# Lab1_Schematics.net
KiCad netlist of a schematic drawn in EAGLE
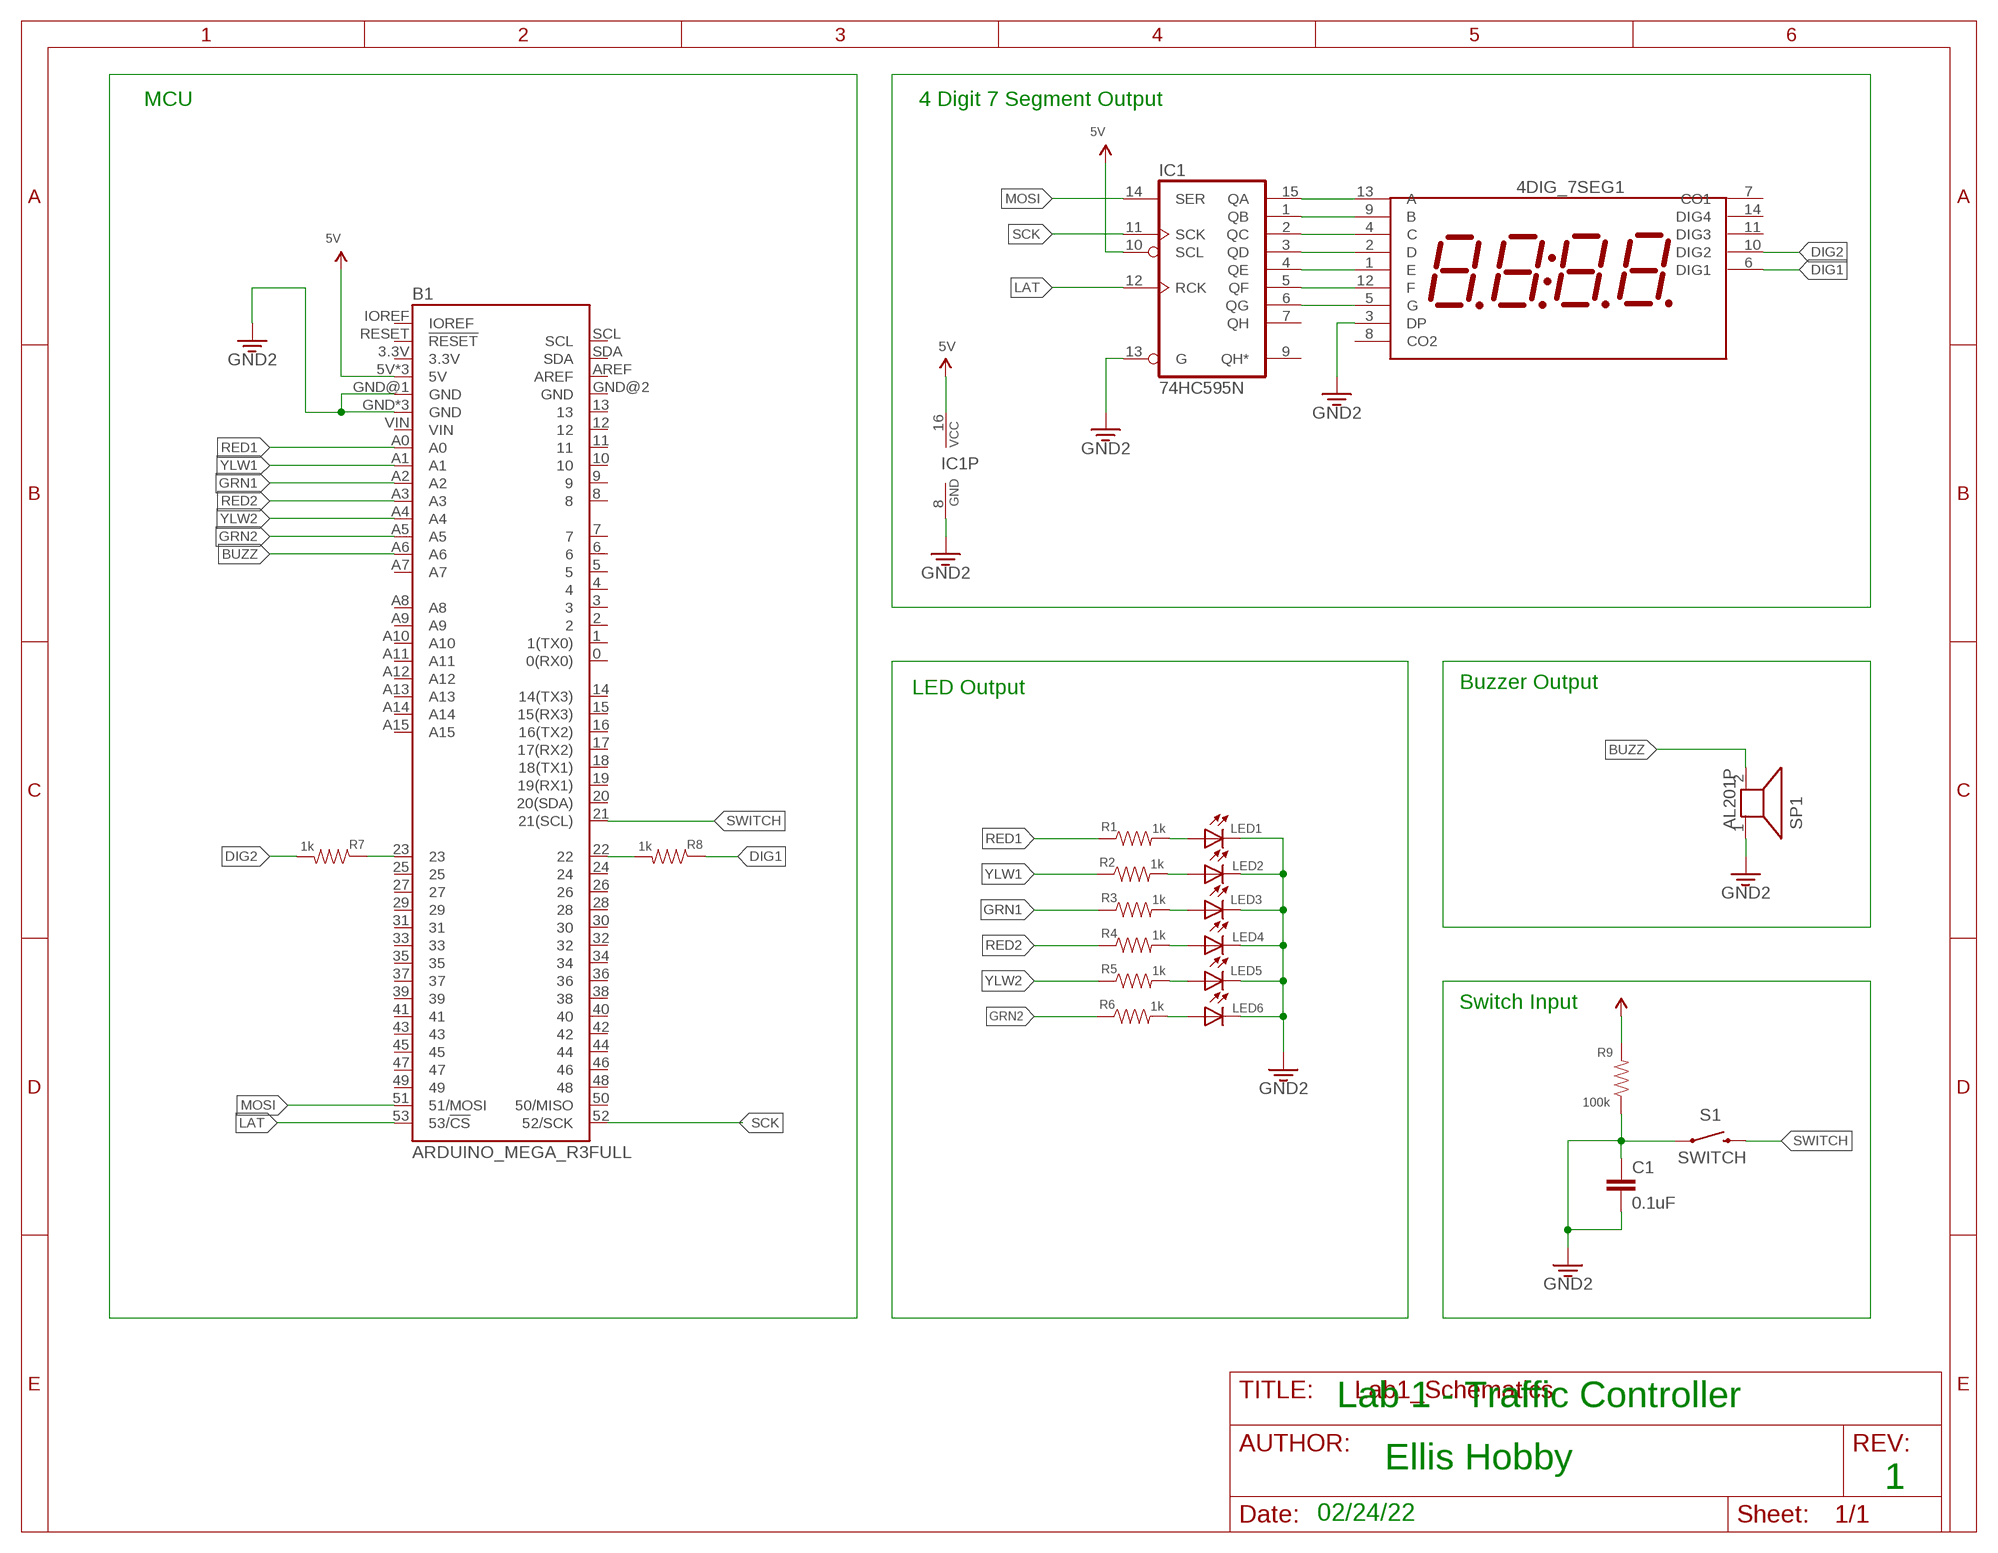
[diagram p0: schematic, sheet 1]

(export (version "E")
  (design (tool "Eeschema 10.0.6"))
  (components
    (comp (ref "4DIG_7SEG1")
      (value "4DIG_7SEG")
      (footprint "eagle-import:4DIG_7SEG")
      (libsource (lib "eagle-import") (part "4DIG_7SEG"))
    )
    (comp (ref "B1")
      (value "ARDUINO_MEGA_R3FULL")
      (footprint "eagle-import:ARDUINO_MEGA_NO_SILK")
      (libsource (lib "eagle-import") (part "ARDUINO_MEGA_R3FULL"))
    )
    (comp (ref "C1")
      (value "0.1uF")
      (footprint "eagle-import:CAP-PTH-SMALL-KIT")
      (libsource (lib "eagle-import") (part "0.1UF-KIT-EZ-50V-20%"))
    )
    (comp (ref "IC1")
      (value "74HC595N")
      (footprint "eagle-import:DIL16")
      (libsource (lib "eagle-import") (part "74595NHC"))
    )
    (comp (ref "LED1")
      (value "LED5MM")
      (footprint "eagle-import:LED5MM")
      (libsource (lib "eagle-import") (part "LED5MM"))
    )
    (comp (ref "LED2")
      (value "LED5MM")
      (footprint "eagle-import:LED5MM")
      (libsource (lib "eagle-import") (part "LED5MM"))
    )
    (comp (ref "LED3")
      (value "LED5MM")
      (footprint "eagle-import:LED5MM")
      (libsource (lib "eagle-import") (part "LED5MM"))
    )
    (comp (ref "LED4")
      (value "LED5MM")
      (footprint "eagle-import:LED5MM")
      (libsource (lib "eagle-import") (part "LED5MM"))
    )
    (comp (ref "LED5")
      (value "LED5MM")
      (footprint "eagle-import:LED5MM")
      (libsource (lib "eagle-import") (part "LED5MM"))
    )
    (comp (ref "LED6")
      (value "LED5MM")
      (footprint "eagle-import:LED5MM")
      (libsource (lib "eagle-import") (part "LED5MM"))
    )
    (comp (ref "R1")
      (value "1k")
      (footprint "eagle-import:AXIAL-0.3")
      (libsource (lib "eagle-import") (part "1KOHM-HORIZ-1/4W-1%"))
    )
    (comp (ref "R2")
      (value "1k")
      (footprint "eagle-import:AXIAL-0.3")
      (libsource (lib "eagle-import") (part "1KOHM-HORIZ-1/4W-1%"))
    )
    (comp (ref "R3")
      (value "1k")
      (footprint "eagle-import:AXIAL-0.3")
      (libsource (lib "eagle-import") (part "1KOHM-HORIZ-1/4W-1%"))
    )
    (comp (ref "R4")
      (value "1k")
      (footprint "eagle-import:AXIAL-0.3")
      (libsource (lib "eagle-import") (part "1KOHM-HORIZ-1/4W-1%"))
    )
    (comp (ref "R5")
      (value "1k")
      (footprint "eagle-import:AXIAL-0.3")
      (libsource (lib "eagle-import") (part "1KOHM-HORIZ-1/4W-1%"))
    )
    (comp (ref "R6")
      (value "1k")
      (footprint "eagle-import:AXIAL-0.3")
      (libsource (lib "eagle-import") (part "1KOHM-HORIZ-1/4W-1%"))
    )
    (comp (ref "R7")
      (value "1k")
      (footprint "eagle-import:AXIAL-0.3")
      (libsource (lib "eagle-import") (part "1KOHM-HORIZ-1/4W-1%"))
    )
    (comp (ref "R8")
      (value "1k")
      (footprint "eagle-import:AXIAL-0.3")
      (libsource (lib "eagle-import") (part "1KOHM-HORIZ-1/4W-1%"))
    )
    (comp (ref "R9")
      (value "100k")
      (footprint "eagle-import:AXIAL-0.3")
      (libsource (lib "eagle-import") (part "1KOHM-HORIZ-1/4W-1%"))
    )
    (comp (ref "S1")
      (value "SWITCH")
      (footprint "eagle-import:TACTILE_SWITCH_PTH_6.0MM")
      (libsource (lib "eagle-import") (part "MOMENTARY-SWITCH-SPST-PTH-6.0MM"))
    )
    (comp (ref "SP1")
      (value "AL201P")
      (footprint "eagle-import:AL201P")
      (libsource (lib "eagle-import") (part "AL201P"))
    )
  )
  (nets
    (net (code "1") (name "5V") (class "Default")
      (node (ref "B1") (pin "5V") (pinfunction "5V_5V") (pintype "bidirectional"))
      (node (ref "B1") (pin "5V@1") (pinfunction "5V_5V@1") (pintype "bidirectional"))
      (node (ref "B1") (pin "5V@2") (pinfunction "5V_5V@2") (pintype "bidirectional"))
      (node (ref "IC1") (pin "10") (pinfunction "SCL_10") (pintype "input"))
      (node (ref "IC1") (pin "16") (pinfunction "VCC_16") (pintype "power_in"))
      (node (ref "R9") (pin "P$2") (pinfunction "2_P$2") (pintype "passive"))
    )
    (net (code "2") (name "BUZZ") (class "Default")
      (node (ref "B1") (pin "A6") (pinfunction "A6_A6") (pintype "bidirectional"))
      (node (ref "SP1") (pin "2") (pinfunction "2_2") (pintype "passive"))
    )
    (net (code "3") (name "DIG1") (class "Default")
      (node (ref "4DIG_7SEG1") (pin "6") (pinfunction "DIG1_6") (pintype "bidirectional"))
      (node (ref "R8") (pin "P$1") (pinfunction "1_P$1") (pintype "passive"))
    )
    (net (code "4") (name "DIG2") (class "Default")
      (node (ref "4DIG_7SEG1") (pin "10") (pinfunction "DIG2_10") (pintype "bidirectional"))
      (node (ref "R7") (pin "P$2") (pinfunction "2_P$2") (pintype "passive"))
    )
    (net (code "5") (name "GND2") (class "Default")
      (node (ref "4DIG_7SEG1") (pin "3") (pinfunction "DP_3") (pintype "bidirectional"))
      (node (ref "B1") (pin "GND") (pinfunction "GND_GND") (pintype "bidirectional"))
      (node (ref "B1") (pin "GND@1") (pinfunction "GND_GND@1") (pintype "bidirectional"))
      (node (ref "B1") (pin "GND@3") (pinfunction "GND_GND@3") (pintype "bidirectional"))
      (node (ref "B1") (pin "GND@4") (pinfunction "GND_GND@4") (pintype "bidirectional"))
      (node (ref "C1") (pin "1") (pinfunction "1_1") (pintype "passive"))
      (node (ref "C1") (pin "2") (pinfunction "2_2") (pintype "passive"))
      (node (ref "IC1") (pin "13") (pinfunction "G_13") (pintype "input"))
      (node (ref "IC1") (pin "8") (pinfunction "GND_8") (pintype "power_in"))
      (node (ref "LED1") (pin "K") (pinfunction "C_K") (pintype "passive"))
      (node (ref "LED2") (pin "K") (pinfunction "C_K") (pintype "passive"))
      (node (ref "LED3") (pin "K") (pinfunction "C_K") (pintype "passive"))
      (node (ref "LED4") (pin "K") (pinfunction "C_K") (pintype "passive"))
      (node (ref "LED5") (pin "K") (pinfunction "C_K") (pintype "passive"))
      (node (ref "LED6") (pin "K") (pinfunction "C_K") (pintype "passive"))
      (node (ref "R9") (pin "P$1") (pinfunction "1_P$1") (pintype "passive"))
      (node (ref "S1") (pin "1") (pinfunction "1_1") (pintype "passive"))
      (node (ref "SP1") (pin "1") (pinfunction "1_1") (pintype "passive"))
    )
    (net (code "6") (name "GRN1") (class "Default")
      (node (ref "B1") (pin "A2") (pinfunction "A2_A2") (pintype "bidirectional"))
      (node (ref "R3") (pin "P$1") (pinfunction "1_P$1") (pintype "passive"))
    )
    (net (code "7") (name "GRN2") (class "Default")
      (node (ref "B1") (pin "A5") (pinfunction "A5_A5") (pintype "bidirectional"))
      (node (ref "R6") (pin "P$1") (pinfunction "1_P$1") (pintype "passive"))
    )
    (net (code "8") (name "LAT") (class "Default")
      (node (ref "B1") (pin "53") (pinfunction "53/~{CS}_53") (pintype "bidirectional"))
      (node (ref "IC1") (pin "12") (pinfunction "RCK_12") (pintype "input"))
    )
    (net (code "9") (name "MOSI") (class "Default")
      (node (ref "B1") (pin "51") (pinfunction "51/MOSI_51") (pintype "bidirectional"))
      (node (ref "IC1") (pin "14") (pinfunction "SER_14") (pintype "input"))
    )
    (net (code "10") (name "Net-(4DIG_7SEG1-A)") (class "Default")
      (node (ref "4DIG_7SEG1") (pin "13") (pinfunction "A_13") (pintype "bidirectional"))
      (node (ref "IC1") (pin "15") (pinfunction "QA_15") (pintype "tri_state"))
    )
    (net (code "11") (name "Net-(4DIG_7SEG1-B)") (class "Default")
      (node (ref "4DIG_7SEG1") (pin "9") (pinfunction "B_9") (pintype "bidirectional"))
      (node (ref "IC1") (pin "1") (pinfunction "QB_1") (pintype "tri_state"))
    )
    (net (code "12") (name "Net-(4DIG_7SEG1-C)") (class "Default")
      (node (ref "4DIG_7SEG1") (pin "4") (pinfunction "C_4") (pintype "bidirectional"))
      (node (ref "IC1") (pin "2") (pinfunction "QC_2") (pintype "tri_state"))
    )
    (net (code "13") (name "Net-(4DIG_7SEG1-D)") (class "Default")
      (node (ref "4DIG_7SEG1") (pin "2") (pinfunction "D_2") (pintype "bidirectional"))
      (node (ref "IC1") (pin "3") (pinfunction "QD_3") (pintype "tri_state"))
    )
    (net (code "14") (name "Net-(4DIG_7SEG1-E)") (class "Default")
      (node (ref "4DIG_7SEG1") (pin "1") (pinfunction "E_1") (pintype "bidirectional"))
      (node (ref "IC1") (pin "4") (pinfunction "QE_4") (pintype "tri_state"))
    )
    (net (code "15") (name "Net-(4DIG_7SEG1-F)") (class "Default")
      (node (ref "4DIG_7SEG1") (pin "12") (pinfunction "F_12") (pintype "bidirectional"))
      (node (ref "IC1") (pin "5") (pinfunction "QF_5") (pintype "tri_state"))
    )
    (net (code "16") (name "Net-(4DIG_7SEG1-G)") (class "Default")
      (node (ref "4DIG_7SEG1") (pin "5") (pinfunction "G_5") (pintype "bidirectional"))
      (node (ref "IC1") (pin "6") (pinfunction "QG_6") (pintype "tri_state"))
    )
    (net (code "17") (name "Net-(R1-2)") (class "Default")
      (node (ref "LED1") (pin "A") (pinfunction "A_A") (pintype "passive"))
      (node (ref "R1") (pin "P$2") (pinfunction "2_P$2") (pintype "passive"))
    )
    (net (code "18") (name "Net-(R2-2)") (class "Default")
      (node (ref "LED2") (pin "A") (pinfunction "A_A") (pintype "passive"))
      (node (ref "R2") (pin "P$2") (pinfunction "2_P$2") (pintype "passive"))
    )
    (net (code "19") (name "Net-(R3-2)") (class "Default")
      (node (ref "LED3") (pin "A") (pinfunction "A_A") (pintype "passive"))
      (node (ref "R3") (pin "P$2") (pinfunction "2_P$2") (pintype "passive"))
    )
    (net (code "20") (name "Net-(R4-2)") (class "Default")
      (node (ref "LED4") (pin "A") (pinfunction "A_A") (pintype "passive"))
      (node (ref "R4") (pin "P$2") (pinfunction "2_P$2") (pintype "passive"))
    )
    (net (code "21") (name "Net-(R5-2)") (class "Default")
      (node (ref "LED5") (pin "A") (pinfunction "A_A") (pintype "passive"))
      (node (ref "R5") (pin "P$2") (pinfunction "2_P$2") (pintype "passive"))
    )
    (net (code "22") (name "Net-(R6-2)") (class "Default")
      (node (ref "LED6") (pin "A") (pinfunction "A_A") (pintype "passive"))
      (node (ref "R6") (pin "P$2") (pinfunction "2_P$2") (pintype "passive"))
    )
    (net (code "23") (name "Net-(R7-1)") (class "Default")
      (node (ref "B1") (pin "23") (pinfunction "23_23") (pintype "bidirectional"))
      (node (ref "R7") (pin "P$1") (pinfunction "1_P$1") (pintype "passive"))
    )
    (net (code "24") (name "Net-(R8-2)") (class "Default")
      (node (ref "B1") (pin "22") (pinfunction "22_22") (pintype "bidirectional"))
      (node (ref "R8") (pin "P$2") (pinfunction "2_P$2") (pintype "passive"))
    )
    (net (code "25") (name "RED1") (class "Default")
      (node (ref "B1") (pin "A0") (pinfunction "A0_A0") (pintype "bidirectional"))
      (node (ref "R1") (pin "P$1") (pinfunction "1_P$1") (pintype "passive"))
    )
    (net (code "26") (name "RED2") (class "Default")
      (node (ref "B1") (pin "A3") (pinfunction "A3_A3") (pintype "bidirectional"))
      (node (ref "R4") (pin "P$1") (pinfunction "1_P$1") (pintype "passive"))
    )
    (net (code "27") (name "SCK") (class "Default")
      (node (ref "B1") (pin "52") (pinfunction "52/SCK_52") (pintype "bidirectional"))
      (node (ref "IC1") (pin "11") (pinfunction "SCK_11") (pintype "input"))
    )
    (net (code "28") (name "SWITCH") (class "Default")
      (node (ref "B1") (pin "21") (pinfunction "21(SCL)_21") (pintype "bidirectional"))
      (node (ref "S1") (pin "3") (pinfunction "2_3") (pintype "passive"))
    )
    (net (code "29") (name "YLW1") (class "Default")
      (node (ref "B1") (pin "A1") (pinfunction "A1_A1") (pintype "bidirectional"))
      (node (ref "R2") (pin "P$1") (pinfunction "1_P$1") (pintype "passive"))
    )
    (net (code "30") (name "YLW2") (class "Default")
      (node (ref "B1") (pin "A4") (pinfunction "A4_A4") (pintype "bidirectional"))
      (node (ref "R5") (pin "P$1") (pinfunction "1_P$1") (pintype "passive"))
    )
    (net (code "31") (name "unconnected-(4DIG_7SEG1-CO1-Pad7)") (class "Default")
      (node (ref "4DIG_7SEG1") (pin "7") (pinfunction "CO1_7") (pintype "bidirectional"))
    )
    (net (code "32") (name "unconnected-(4DIG_7SEG1-CO2-Pad8)") (class "Default")
      (node (ref "4DIG_7SEG1") (pin "8") (pinfunction "CO2_8") (pintype "bidirectional"))
    )
    (net (code "33") (name "unconnected-(4DIG_7SEG1-DIG3-Pad11)") (class "Default")
      (node (ref "4DIG_7SEG1") (pin "11") (pinfunction "DIG3_11") (pintype "bidirectional"))
    )
    (net (code "34") (name "unconnected-(4DIG_7SEG1-DIG4-Pad14)") (class "Default")
      (node (ref "4DIG_7SEG1") (pin "14") (pinfunction "DIG4_14") (pintype "bidirectional"))
    )
    (net (code "35") (name "unconnected-(B1-0(RX0)-Pad0)") (class "Default")
      (node (ref "B1") (pin "0") (pinfunction "0(RX0)_0") (pintype "bidirectional"))
    )
    (net (code "36") (name "unconnected-(B1-1(TX0)-Pad1)") (class "Default")
      (node (ref "B1") (pin "1") (pinfunction "1(TX0)_1") (pintype "bidirectional"))
    )
    (net (code "37") (name "unconnected-(B1-14(TX3)-Pad14)") (class "Default")
      (node (ref "B1") (pin "14") (pinfunction "14(TX3)_14") (pintype "bidirectional"))
    )
    (net (code "38") (name "unconnected-(B1-15(RX3)-Pad15)") (class "Default")
      (node (ref "B1") (pin "15") (pinfunction "15(RX3)_15") (pintype "bidirectional"))
    )
    (net (code "39") (name "unconnected-(B1-16(TX2)-Pad16)") (class "Default")
      (node (ref "B1") (pin "16") (pinfunction "16(TX2)_16") (pintype "bidirectional"))
    )
    (net (code "40") (name "unconnected-(B1-17(RX2)-Pad17)") (class "Default")
      (node (ref "B1") (pin "17") (pinfunction "17(RX2)_17") (pintype "bidirectional"))
    )
    (net (code "41") (name "unconnected-(B1-18(TX1)-Pad18)") (class "Default")
      (node (ref "B1") (pin "18") (pinfunction "18(TX1)_18") (pintype "bidirectional"))
    )
    (net (code "42") (name "unconnected-(B1-19(RX1)-Pad19)") (class "Default")
      (node (ref "B1") (pin "19") (pinfunction "19(RX1)_19") (pintype "bidirectional"))
    )
    (net (code "43") (name "unconnected-(B1-20(SDA)-Pad20)") (class "Default")
      (node (ref "B1") (pin "20") (pinfunction "20(SDA)_20") (pintype "bidirectional"))
    )
    (net (code "44") (name "unconnected-(B1-50{slash}MISO-Pad50)") (class "Default")
      (node (ref "B1") (pin "50") (pinfunction "50/MISO_50") (pintype "bidirectional"))
    )
    (net (code "45") (name "unconnected-(B1-GND-PadGND@2)") (class "Default")
      (node (ref "B1") (pin "GND@2") (pinfunction "GND_GND@2") (pintype "bidirectional"))
    )
    (net (code "46") (name "unconnected-(B1-Pad2)") (class "Default")
      (node (ref "B1") (pin "2") (pinfunction "2_2") (pintype "bidirectional"))
    )
    (net (code "47") (name "unconnected-(B1-Pad3)") (class "Default")
      (node (ref "B1") (pin "3") (pinfunction "3_3") (pintype "bidirectional"))
    )
    (net (code "48") (name "unconnected-(B1-Pad3.3V)") (class "Default")
      (node (ref "B1") (pin "3.3V") (pinfunction "3.3V_3.3V") (pintype "bidirectional"))
    )
    (net (code "49") (name "unconnected-(B1-Pad4)") (class "Default")
      (node (ref "B1") (pin "4") (pinfunction "4_4") (pintype "bidirectional"))
    )
    (net (code "50") (name "unconnected-(B1-Pad5)") (class "Default")
      (node (ref "B1") (pin "5") (pinfunction "5_5") (pintype "bidirectional"))
    )
    (net (code "51") (name "unconnected-(B1-Pad6)") (class "Default")
      (node (ref "B1") (pin "6") (pinfunction "6_6") (pintype "bidirectional"))
    )
    (net (code "52") (name "unconnected-(B1-Pad7)") (class "Default")
      (node (ref "B1") (pin "7") (pinfunction "7_7") (pintype "bidirectional"))
    )
    (net (code "53") (name "unconnected-(B1-Pad8)") (class "Default")
      (node (ref "B1") (pin "8") (pinfunction "8_8") (pintype "bidirectional"))
    )
    (net (code "54") (name "unconnected-(B1-Pad9)") (class "Default")
      (node (ref "B1") (pin "9") (pinfunction "9_9") (pintype "bidirectional"))
    )
    (net (code "55") (name "unconnected-(B1-Pad10)") (class "Default")
      (node (ref "B1") (pin "10") (pinfunction "10_10") (pintype "bidirectional"))
    )
    (net (code "56") (name "unconnected-(B1-Pad11)") (class "Default")
      (node (ref "B1") (pin "11") (pinfunction "11_11") (pintype "bidirectional"))
    )
    (net (code "57") (name "unconnected-(B1-Pad12)") (class "Default")
      (node (ref "B1") (pin "12") (pinfunction "12_12") (pintype "bidirectional"))
    )
    (net (code "58") (name "unconnected-(B1-Pad13)") (class "Default")
      (node (ref "B1") (pin "13") (pinfunction "13_13") (pintype "bidirectional"))
    )
    (net (code "59") (name "unconnected-(B1-Pad24)") (class "Default")
      (node (ref "B1") (pin "24") (pinfunction "24_24") (pintype "bidirectional"))
    )
    (net (code "60") (name "unconnected-(B1-Pad25)") (class "Default")
      (node (ref "B1") (pin "25") (pinfunction "25_25") (pintype "bidirectional"))
    )
    (net (code "61") (name "unconnected-(B1-Pad26)") (class "Default")
      (node (ref "B1") (pin "26") (pinfunction "26_26") (pintype "bidirectional"))
    )
    (net (code "62") (name "unconnected-(B1-Pad27)") (class "Default")
      (node (ref "B1") (pin "27") (pinfunction "27_27") (pintype "bidirectional"))
    )
    (net (code "63") (name "unconnected-(B1-Pad28)") (class "Default")
      (node (ref "B1") (pin "28") (pinfunction "28_28") (pintype "bidirectional"))
    )
    (net (code "64") (name "unconnected-(B1-Pad29)") (class "Default")
      (node (ref "B1") (pin "29") (pinfunction "29_29") (pintype "bidirectional"))
    )
    (net (code "65") (name "unconnected-(B1-Pad30)") (class "Default")
      (node (ref "B1") (pin "30") (pinfunction "30_30") (pintype "bidirectional"))
    )
    (net (code "66") (name "unconnected-(B1-Pad31)") (class "Default")
      (node (ref "B1") (pin "31") (pinfunction "31_31") (pintype "bidirectional"))
    )
    (net (code "67") (name "unconnected-(B1-Pad32)") (class "Default")
      (node (ref "B1") (pin "32") (pinfunction "32_32") (pintype "bidirectional"))
    )
    (net (code "68") (name "unconnected-(B1-Pad33)") (class "Default")
      (node (ref "B1") (pin "33") (pinfunction "33_33") (pintype "bidirectional"))
    )
    (net (code "69") (name "unconnected-(B1-Pad34)") (class "Default")
      (node (ref "B1") (pin "34") (pinfunction "34_34") (pintype "bidirectional"))
    )
    (net (code "70") (name "unconnected-(B1-Pad35)") (class "Default")
      (node (ref "B1") (pin "35") (pinfunction "35_35") (pintype "bidirectional"))
    )
    (net (code "71") (name "unconnected-(B1-Pad36)") (class "Default")
      (node (ref "B1") (pin "36") (pinfunction "36_36") (pintype "bidirectional"))
    )
    (net (code "72") (name "unconnected-(B1-Pad37)") (class "Default")
      (node (ref "B1") (pin "37") (pinfunction "37_37") (pintype "bidirectional"))
    )
    (net (code "73") (name "unconnected-(B1-Pad38)") (class "Default")
      (node (ref "B1") (pin "38") (pinfunction "38_38") (pintype "bidirectional"))
    )
    (net (code "74") (name "unconnected-(B1-Pad39)") (class "Default")
      (node (ref "B1") (pin "39") (pinfunction "39_39") (pintype "bidirectional"))
    )
    (net (code "75") (name "unconnected-(B1-Pad40)") (class "Default")
      (node (ref "B1") (pin "40") (pinfunction "40_40") (pintype "bidirectional"))
    )
    (net (code "76") (name "unconnected-(B1-Pad41)") (class "Default")
      (node (ref "B1") (pin "41") (pinfunction "41_41") (pintype "bidirectional"))
    )
    (net (code "77") (name "unconnected-(B1-Pad42)") (class "Default")
      (node (ref "B1") (pin "42") (pinfunction "42_42") (pintype "bidirectional"))
    )
    (net (code "78") (name "unconnected-(B1-Pad43)") (class "Default")
      (node (ref "B1") (pin "43") (pinfunction "43_43") (pintype "bidirectional"))
    )
    (net (code "79") (name "unconnected-(B1-Pad44)") (class "Default")
      (node (ref "B1") (pin "44") (pinfunction "44_44") (pintype "bidirectional"))
    )
    (net (code "80") (name "unconnected-(B1-Pad45)") (class "Default")
      (node (ref "B1") (pin "45") (pinfunction "45_45") (pintype "bidirectional"))
    )
    (net (code "81") (name "unconnected-(B1-Pad46)") (class "Default")
      (node (ref "B1") (pin "46") (pinfunction "46_46") (pintype "bidirectional"))
    )
    (net (code "82") (name "unconnected-(B1-Pad47)") (class "Default")
      (node (ref "B1") (pin "47") (pinfunction "47_47") (pintype "bidirectional"))
    )
    (net (code "83") (name "unconnected-(B1-Pad48)") (class "Default")
      (node (ref "B1") (pin "48") (pinfunction "48_48") (pintype "bidirectional"))
    )
    (net (code "84") (name "unconnected-(B1-Pad49)") (class "Default")
      (node (ref "B1") (pin "49") (pinfunction "49_49") (pintype "bidirectional"))
    )
    (net (code "85") (name "unconnected-(B1-PadA7)") (class "Default")
      (node (ref "B1") (pin "A7") (pinfunction "A7_A7") (pintype "bidirectional"))
    )
    (net (code "86") (name "unconnected-(B1-PadA8)") (class "Default")
      (node (ref "B1") (pin "A8") (pinfunction "A8_A8") (pintype "bidirectional"))
    )
    (net (code "87") (name "unconnected-(B1-PadA9)") (class "Default")
      (node (ref "B1") (pin "A9") (pinfunction "A9_A9") (pintype "bidirectional"))
    )
    (net (code "88") (name "unconnected-(B1-PadA10)") (class "Default")
      (node (ref "B1") (pin "A10") (pinfunction "A10_A10") (pintype "bidirectional"))
    )
    (net (code "89") (name "unconnected-(B1-PadA11)") (class "Default")
      (node (ref "B1") (pin "A11") (pinfunction "A11_A11") (pintype "bidirectional"))
    )
    (net (code "90") (name "unconnected-(B1-PadA12)") (class "Default")
      (node (ref "B1") (pin "A12") (pinfunction "A12_A12") (pintype "bidirectional"))
    )
    (net (code "91") (name "unconnected-(B1-PadA13)") (class "Default")
      (node (ref "B1") (pin "A13") (pinfunction "A13_A13") (pintype "bidirectional"))
    )
    (net (code "92") (name "unconnected-(B1-PadA14)") (class "Default")
      (node (ref "B1") (pin "A14") (pinfunction "A14_A14") (pintype "bidirectional"))
    )
    (net (code "93") (name "unconnected-(B1-PadA15)") (class "Default")
      (node (ref "B1") (pin "A15") (pinfunction "A15_A15") (pintype "bidirectional"))
    )
    (net (code "94") (name "unconnected-(B1-PadAREF)") (class "Default")
      (node (ref "B1") (pin "AREF") (pinfunction "AREF_AREF") (pintype "bidirectional"))
    )
    (net (code "95") (name "unconnected-(B1-PadIOREF)") (class "Default")
      (node (ref "B1") (pin "IOREF") (pinfunction "IOREF_IOREF") (pintype "bidirectional"))
    )
    (net (code "96") (name "unconnected-(B1-PadSCL)") (class "Default")
      (node (ref "B1") (pin "SCL") (pinfunction "SCL_SCL") (pintype "bidirectional"))
    )
    (net (code "97") (name "unconnected-(B1-PadSDA)") (class "Default")
      (node (ref "B1") (pin "SDA") (pinfunction "SDA_SDA") (pintype "bidirectional"))
    )
    (net (code "98") (name "unconnected-(B1-PadVIN)") (class "Default")
      (node (ref "B1") (pin "VIN") (pinfunction "VIN_VIN") (pintype "bidirectional"))
    )
    (net (code "99") (name "unconnected-(B1-~{RESET}-PadRESET)") (class "Default")
      (node (ref "B1") (pin "RESET") (pinfunction "~{RESET}_RESET") (pintype "bidirectional"))
    )
    (net (code "100") (name "unconnected-(IC1A-QH*-Pad9)") (class "Default")
      (node (ref "IC1") (pin "9") (pinfunction "QH*_9") (pintype "tri_state"))
    )
    (net (code "101") (name "unconnected-(IC1A-QH-Pad7)") (class "Default")
      (node (ref "IC1") (pin "7") (pinfunction "QH_7") (pintype "tri_state"))
    )
  )
)
